# SW_DIP8.net
KiCad netlist of a schematic drawn in Altium Designer
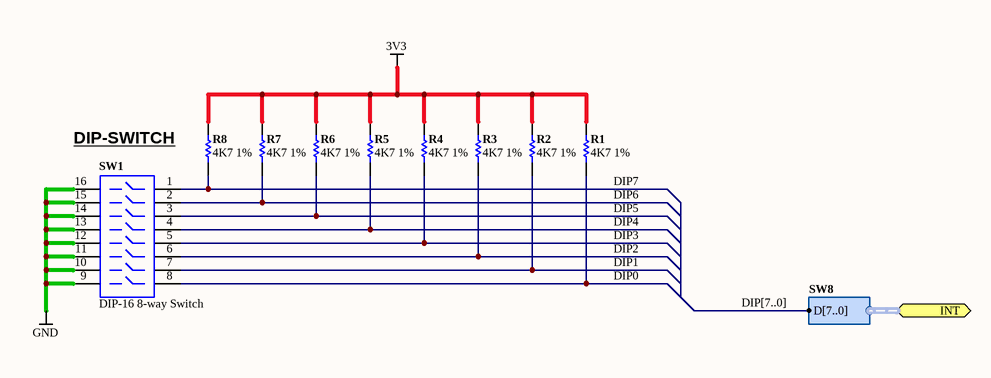
[diagram p0: SW_DIP8.SchDoc]

(export (version "E")
  (design (tool "Eeschema 10.0.6"))
  (components
    (comp (ref "R1")
      (value "4K7 1%")
      (footprint "RESC1005-STAR")
      (description "Resistor, 4K7 1% 0402 (1005)")
      (fields (field (name "TOLERANCE") "1 %"))
      (libsource (lib "altium-import") (part "root_2_RES_"))
    )
    (comp (ref "R2")
      (value "4K7 1%")
      (footprint "RESC1005-STAR")
      (description "Resistor, 4K7 1% 0402 (1005)")
      (fields (field (name "TOLERANCE") "1 %"))
      (libsource (lib "altium-import") (part "root_2_RES_"))
    )
    (comp (ref "R3")
      (value "4K7 1%")
      (footprint "RESC1005-STAR")
      (description "Resistor, 4K7 1% 0402 (1005)")
      (fields (field (name "TOLERANCE") "1 %"))
      (libsource (lib "altium-import") (part "root_2_RES_"))
    )
    (comp (ref "R4")
      (value "4K7 1%")
      (footprint "RESC1005-STAR")
      (description "Resistor, 4K7 1% 0402 (1005)")
      (fields (field (name "TOLERANCE") "1 %"))
      (libsource (lib "altium-import") (part "root_2_RES_"))
    )
    (comp (ref "R5")
      (value "4K7 1%")
      (footprint "RESC1005-STAR")
      (description "Resistor, 4K7 1% 0402 (1005)")
      (fields (field (name "TOLERANCE") "1 %"))
      (libsource (lib "altium-import") (part "root_2_RES_"))
    )
    (comp (ref "R6")
      (value "4K7 1%")
      (footprint "RESC1005-STAR")
      (description "Resistor, 4K7 1% 0402 (1005)")
      (fields (field (name "TOLERANCE") "1 %"))
      (libsource (lib "altium-import") (part "root_2_RES_"))
    )
    (comp (ref "R7")
      (value "4K7 1%")
      (footprint "RESC1005-STAR")
      (description "Resistor, 4K7 1% 0402 (1005)")
      (fields (field (name "TOLERANCE") "1 %"))
      (libsource (lib "altium-import") (part "root_2_RES_"))
    )
    (comp (ref "R8")
      (value "4K7 1%")
      (footprint "RESC1005-STAR")
      (description "Resistor, 4K7 1% 0402 (1005)")
      (fields (field (name "TOLERANCE") "1 %"))
      (libsource (lib "altium-import") (part "root_2_RES_"))
    )
    (comp (ref "SW1")
      (value "DIP-16 8-way Switch")
      (footprint "DIP-16-KEY")
      (description "Switch, DIP Black 8-Way 300mil x 100mil")
      (libsource (lib "AltiumDesignLibrary") (part "SWI-DIP-8"))
    )
  )
  (nets
    (net (code "2") (name "/DIP0") (class "Default")
      (node (ref "R1") (pin "1") (pinfunction "1_1") (pintype "passive"))
      (node (ref "SW1") (pin "8") (pinfunction "8_8") (pintype "passive"))
    )
    (net (code "3") (name "/DIP1") (class "Default")
      (node (ref "R2") (pin "1") (pinfunction "1_1") (pintype "passive"))
      (node (ref "SW1") (pin "7") (pinfunction "7_7") (pintype "passive"))
    )
    (net (code "4") (name "/DIP2") (class "Default")
      (node (ref "R3") (pin "1") (pinfunction "1_1") (pintype "passive"))
      (node (ref "SW1") (pin "6") (pinfunction "6_6") (pintype "passive"))
    )
    (net (code "5") (name "/DIP3") (class "Default")
      (node (ref "R4") (pin "1") (pinfunction "1_1") (pintype "passive"))
      (node (ref "SW1") (pin "5") (pinfunction "5_5") (pintype "passive"))
    )
    (net (code "6") (name "/DIP4") (class "Default")
      (node (ref "R5") (pin "1") (pinfunction "1_1") (pintype "passive"))
      (node (ref "SW1") (pin "4") (pinfunction "4_4") (pintype "passive"))
    )
    (net (code "7") (name "/DIP5") (class "Default")
      (node (ref "R6") (pin "1") (pinfunction "1_1") (pintype "passive"))
      (node (ref "SW1") (pin "3") (pinfunction "3_3") (pintype "passive"))
    )
    (net (code "8") (name "/DIP6") (class "Default")
      (node (ref "R7") (pin "1") (pinfunction "1_1") (pintype "passive"))
      (node (ref "SW1") (pin "2") (pinfunction "2_2") (pintype "passive"))
    )
    (net (code "9") (name "/DIP7") (class "Default")
      (node (ref "R8") (pin "1") (pinfunction "1_1") (pintype "passive"))
      (node (ref "SW1") (pin "1") (pinfunction "1_1") (pintype "passive"))
    )
    (net (code "12") (name "3V3") (class "Default")
      (node (ref "R1") (pin "2") (pinfunction "2_2") (pintype "passive"))
      (node (ref "R2") (pin "2") (pinfunction "2_2") (pintype "passive"))
      (node (ref "R3") (pin "2") (pinfunction "2_2") (pintype "passive"))
      (node (ref "R4") (pin "2") (pinfunction "2_2") (pintype "passive"))
      (node (ref "R5") (pin "2") (pinfunction "2_2") (pintype "passive"))
      (node (ref "R6") (pin "2") (pinfunction "2_2") (pintype "passive"))
      (node (ref "R7") (pin "2") (pinfunction "2_2") (pintype "passive"))
      (node (ref "R8") (pin "2") (pinfunction "2_2") (pintype "passive"))
    )
    (net (code "13") (name "GND") (class "Default")
      (node (ref "SW1") (pin "10") (pinfunction "10_10") (pintype "passive"))
      (node (ref "SW1") (pin "11") (pinfunction "11_11") (pintype "passive"))
      (node (ref "SW1") (pin "12") (pinfunction "12_12") (pintype "passive"))
      (node (ref "SW1") (pin "13") (pinfunction "13_13") (pintype "passive"))
      (node (ref "SW1") (pin "14") (pinfunction "14_14") (pintype "passive"))
      (node (ref "SW1") (pin "15") (pinfunction "15_15") (pintype "passive"))
      (node (ref "SW1") (pin "16") (pinfunction "16_16") (pintype "passive"))
      (node (ref "SW1") (pin "9") (pinfunction "9_9") (pintype "passive"))
    )
  )
)
